# Adafruit_eInk_Feather_Friend.net
KiCad netlist of a schematic drawn in EAGLE
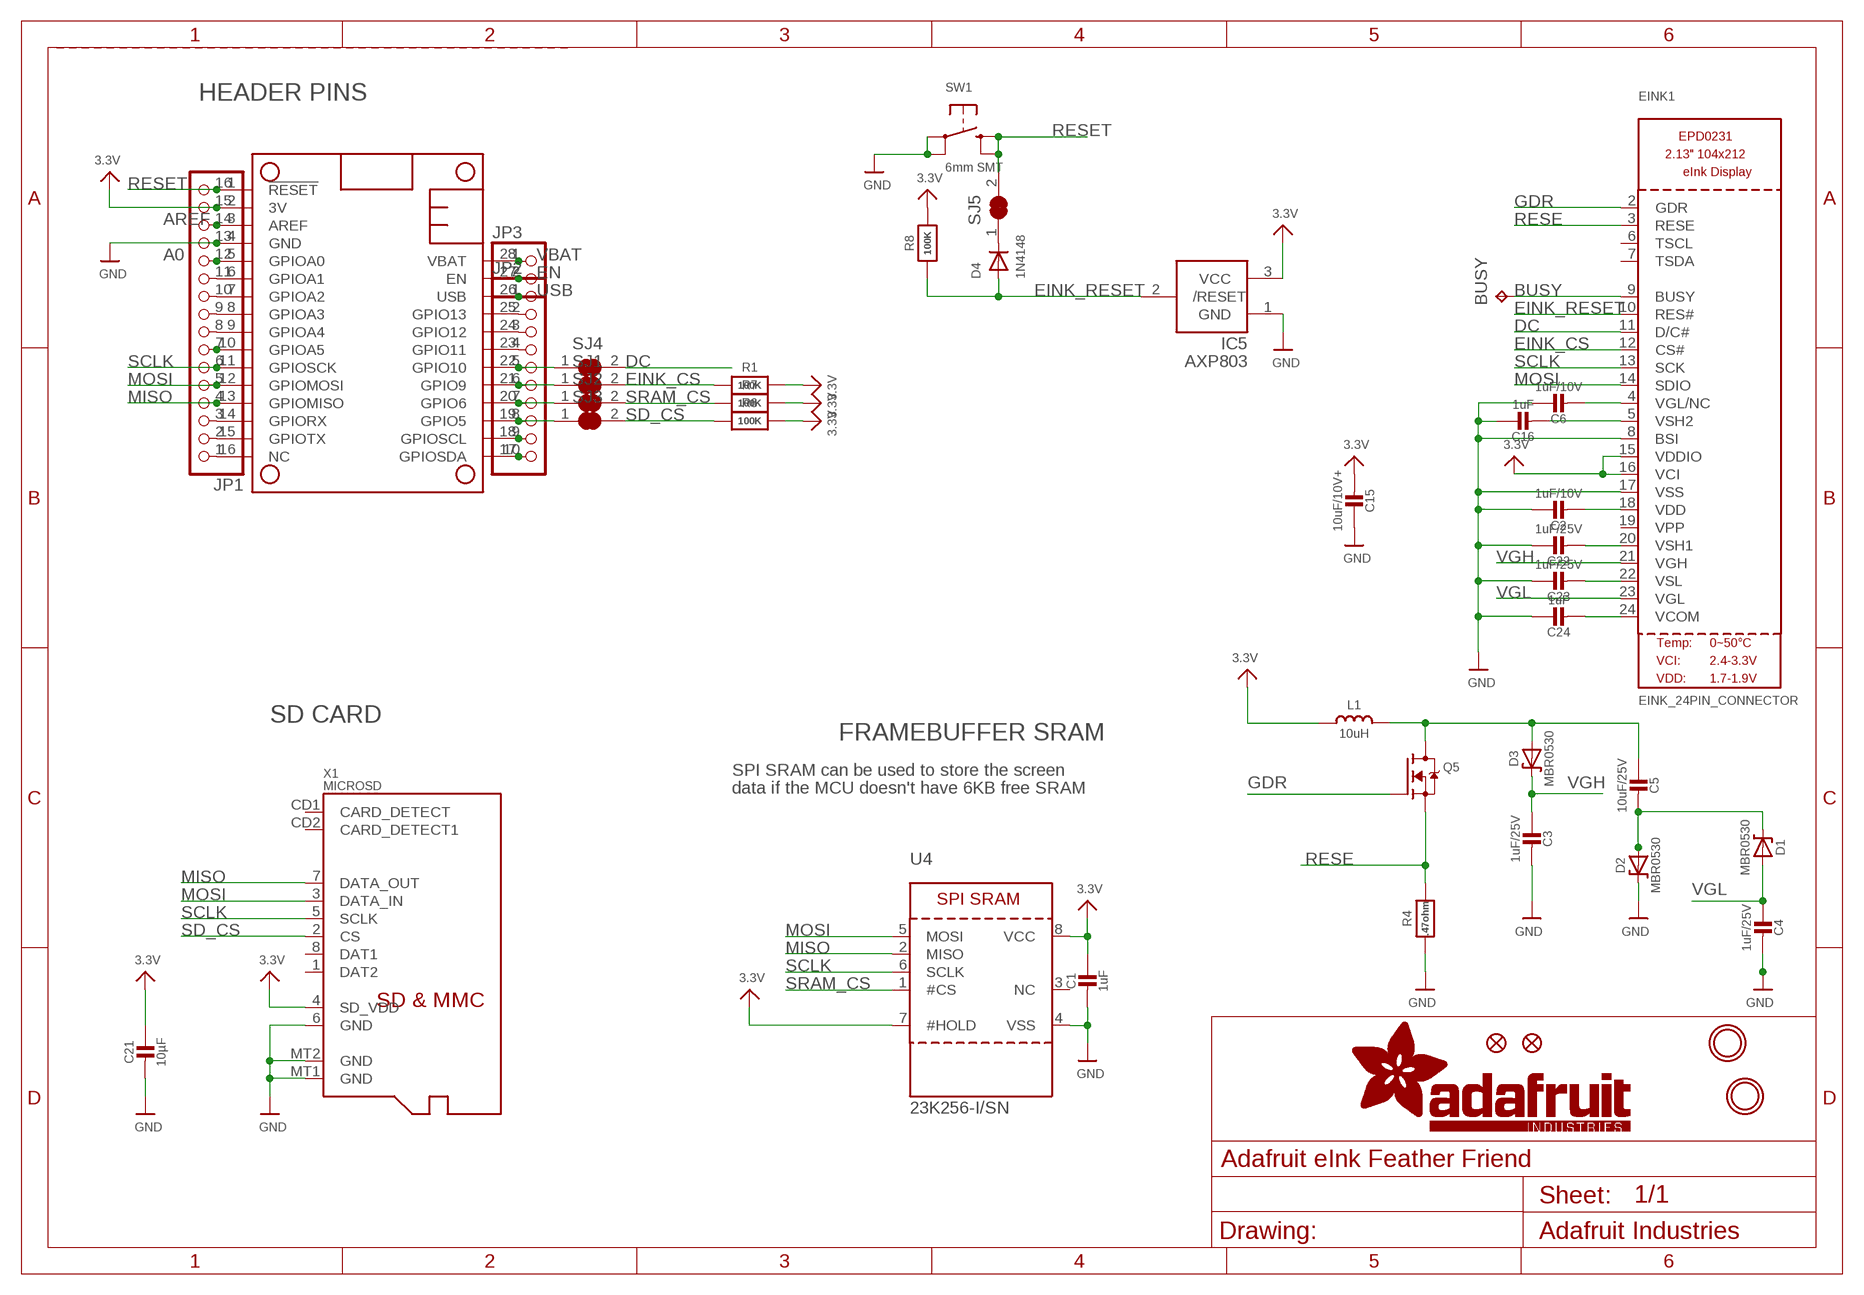
[diagram p0: schematic, sheet 1]

(export (version "E")
  (design (tool "Eeschema 10.0.6"))
  (components
    (comp (ref "BUSY")
      (value "TPTP15SQ")
      (footprint "eagle-import:TP15SQ")
      (libsource (lib "eagle-import") (part "TPTP15SQ"))
    )
    (comp (ref "C1")
      (value "1uF")
      (footprint "eagle-import:0805_10MGAP")
      (fields (field (name "REV") "A"))
      (libsource (lib "eagle-import") (part "CAP_CERAMIC0805_10MGAP"))
    )
    (comp (ref "C2")
      (value "1uF/10V")
      (footprint "eagle-import:0805-NO")
      (libsource (lib "eagle-import") (part "CAP_CERAMIC0805-NOOUTLINE"))
    )
    (comp (ref "C3")
      (value "1uF/25V")
      (footprint "eagle-import:0805-NO")
      (libsource (lib "eagle-import") (part "CAP_CERAMIC0805-NOOUTLINE"))
    )
    (comp (ref "C4")
      (value "1uF/25V")
      (footprint "eagle-import:0805-NO")
      (libsource (lib "eagle-import") (part "CAP_CERAMIC0805-NOOUTLINE"))
    )
    (comp (ref "C5")
      (value "10uF/25V")
      (footprint "eagle-import:0805-NO")
      (libsource (lib "eagle-import") (part "CAP_CERAMIC0805-NOOUTLINE"))
    )
    (comp (ref "C6")
      (value "1uF/10V")
      (footprint "eagle-import:0805-NO")
      (libsource (lib "eagle-import") (part "CAP_CERAMIC0805-NOOUTLINE"))
    )
    (comp (ref "C15")
      (value "10uF/10V+")
      (footprint "eagle-import:0805-NO")
      (libsource (lib "eagle-import") (part "CAP_CERAMIC0805-NOOUTLINE"))
    )
    (comp (ref "C16")
      (value "1uF")
      (footprint "eagle-import:0805-NO")
      (libsource (lib "eagle-import") (part "CAP_CERAMIC0805-NOOUTLINE"))
    )
    (comp (ref "C21")
      (value "10µF")
      (footprint "eagle-import:0805-NO")
      (libsource (lib "eagle-import") (part "CAP_CERAMIC0805-NOOUTLINE"))
    )
    (comp (ref "C22")
      (value "1uF/25V")
      (footprint "eagle-import:0805-NO")
      (libsource (lib "eagle-import") (part "CAP_CERAMIC0805-NOOUTLINE"))
    )
    (comp (ref "C23")
      (value "1uF/25V")
      (footprint "eagle-import:0805-NO")
      (libsource (lib "eagle-import") (part "CAP_CERAMIC0805-NOOUTLINE"))
    )
    (comp (ref "C24")
      (value "1uF")
      (footprint "eagle-import:0805-NO")
      (libsource (lib "eagle-import") (part "CAP_CERAMIC0805-NOOUTLINE"))
    )
    (comp (ref "D1")
      (value "MBR0530")
      (footprint "eagle-import:SOD-123")
      (libsource (lib "eagle-import") (part "DIODE-SCHOTTKYSOD-123"))
    )
    (comp (ref "D2")
      (value "MBR0530")
      (footprint "eagle-import:SOD-123")
      (libsource (lib "eagle-import") (part "DIODE-SCHOTTKYSOD-123"))
    )
    (comp (ref "D3")
      (value "MBR0530")
      (footprint "eagle-import:SOD-123")
      (libsource (lib "eagle-import") (part "DIODE-SCHOTTKYSOD-123"))
    )
    (comp (ref "D4")
      (value "1N4148")
      (footprint "eagle-import:SOD-323F")
      (libsource (lib "eagle-import") (part "DIODESOD-323F"))
    )
    (comp (ref "EINK1")
      (value "EINK_24PIN_CONNECTOR")
      (footprint "eagle-import:EINK_24PIN")
      (libsource (lib "eagle-import") (part "EINK_24PIN_CONNECTOR"))
    )
    (comp (ref "FID1")
      (value "FIDUCIAL_1MM")
      (footprint "eagle-import:FIDUCIAL_1MM")
      (libsource (lib "eagle-import") (part "FIDUCIAL_1MM"))
    )
    (comp (ref "FID3")
      (value "FIDUCIAL_1MM")
      (footprint "eagle-import:FIDUCIAL_1MM")
      (libsource (lib "eagle-import") (part "FIDUCIAL_1MM"))
    )
    (comp (ref "IC5")
      (value "AXP803")
      (footprint "eagle-import:SOT23")
      (libsource (lib "eagle-import") (part "AXP083-SAG"))
    )
    (comp (ref "JP1")
      (value "HEADER-1X16ROUND")
      (footprint "eagle-import:1X16_ROUND")
      (libsource (lib "eagle-import") (part "HEADER-1X16ROUND"))
    )
    (comp (ref "JP2")
      (value "HEADER-1X10ROUND")
      (footprint "eagle-import:1X10_ROUND")
      (libsource (lib "eagle-import") (part "HEADER-1X10ROUND"))
    )
    (comp (ref "JP3")
      (value "HEADER-1X2ROUND")
      (footprint "eagle-import:1X02_ROUND")
      (libsource (lib "eagle-import") (part "HEADER-1X2ROUND"))
    )
    (comp (ref "L1")
      (value "10uH")
      (footprint "eagle-import:INDUCTOR_4X4MM_NR401")
      (libsource (lib "eagle-import") (part "INDUCTORNR401"))
    )
    (comp (ref "MS1")
      (value "FEATHERWING_NOHOLES")
      (footprint "eagle-import:FEATHERWING_NOHOLES")
      (libsource (lib "eagle-import") (part "FEATHERWING_NOHOLES"))
    )
    (comp (ref "Q5")
      (value "IRLML0100")
      (footprint "eagle-import:SOT23-3")
      (libsource (lib "eagle-import") (part "IRLML2060TRPBF"))
    )
    (comp (ref "R1")
      (value "100K")
      (footprint "eagle-import:0603-NO")
      (libsource (lib "eagle-import") (part "RESISTOR_0603_NOOUT"))
    )
    (comp (ref "R4")
      (value ".47ohm")
      (footprint "eagle-import:0805_10MGAP")
      (libsource (lib "eagle-import") (part "RESISTOR0805_10MGAP"))
    )
    (comp (ref "R6")
      (value "100K")
      (footprint "eagle-import:0603-NO")
      (libsource (lib "eagle-import") (part "RESISTOR_0603_NOOUT"))
    )
    (comp (ref "R7")
      (value "100K")
      (footprint "eagle-import:0603-NO")
      (libsource (lib "eagle-import") (part "RESISTOR_0603_NOOUT"))
    )
    (comp (ref "R8")
      (value "100K")
      (footprint "eagle-import:0603-NO")
      (libsource (lib "eagle-import") (part "RESISTOR_0603_NOOUT"))
    )
    (comp (ref "SJ1")
      (value "SOLDERJUMPER_CLOSED")
      (footprint "eagle-import:SOLDERJUMPER_CLOSEDWIRE")
      (libsource (lib "eagle-import") (part "SOLDERJUMPER_CLOSED"))
    )
    (comp (ref "SJ2")
      (value "SOLDERJUMPER_CLOSED")
      (footprint "eagle-import:SOLDERJUMPER_CLOSEDWIRE")
      (libsource (lib "eagle-import") (part "SOLDERJUMPER_CLOSED"))
    )
    (comp (ref "SJ3")
      (value "SOLDERJUMPER_CLOSED")
      (footprint "eagle-import:SOLDERJUMPER_CLOSEDWIRE")
      (libsource (lib "eagle-import") (part "SOLDERJUMPER_CLOSED"))
    )
    (comp (ref "SJ4")
      (value "SOLDERJUMPER_CLOSED")
      (footprint "eagle-import:SOLDERJUMPER_CLOSEDWIRE")
      (libsource (lib "eagle-import") (part "SOLDERJUMPER_CLOSED"))
    )
    (comp (ref "SJ5")
      (value "SOLDERJUMPER_CLOSED")
      (footprint "eagle-import:SOLDERJUMPER_CLOSEDWIRE")
      (libsource (lib "eagle-import") (part "SOLDERJUMPER_CLOSED"))
    )
    (comp (ref "SW1")
      (value "6mm SMT")
      (footprint "eagle-import:BTN_KMR2_4.6X2.8")
      (libsource (lib "eagle-import") (part "SWITCH_TACT_SMT4.6X2.8"))
    )
    (comp (ref "U$3")
      (value "MOUNTINGHOLE2.5")
      (footprint "eagle-import:MOUNTINGHOLE_2.5_PLATED")
      (libsource (lib "eagle-import") (part "MOUNTINGHOLE2.5"))
    )
    (comp (ref "U$4")
      (value "MOUNTINGHOLE2.5")
      (footprint "eagle-import:MOUNTINGHOLE_2.5_PLATED")
      (libsource (lib "eagle-import") (part "MOUNTINGHOLE2.5"))
    )
    (comp (ref "U4")
      (value "23K256-I/SN")
      (footprint "eagle-import:SOIC8_150MIL")
      (libsource (lib "eagle-import") (part "SRAM_SPI_SOIC8"))
    )
    (comp (ref "X1")
      (value "MICROSD")
      (footprint "eagle-import:MICROSD")
      (libsource (lib "eagle-import") (part "MICROSD"))
    )
  )
  (nets
    (net (code "3") (name "/A0") (class "Default")
      (node (ref "JP1") (pin "12") (pinfunction "12_12") (pintype "passive"))
      (node (ref "MS1") (pin "5") (pinfunction "GPIOA0_5") (pintype "bidirectional"))
    )
    (net (code "4") (name "/AREF") (class "Default")
      (node (ref "JP1") (pin "14") (pinfunction "14_14") (pintype "passive"))
      (node (ref "MS1") (pin "3") (pinfunction "AREF_3") (pintype "passive"))
    )
    (net (code "5") (name "/BUSY") (class "Default")
      (node (ref "BUSY") (pin "TP") (pinfunction "TP_TP") (pintype "input"))
      (node (ref "EINK1") (pin "9") (pinfunction "BUSY_9") (pintype "output"))
    )
    (net (code "6") (name "/DC") (class "Default")
      (node (ref "EINK1") (pin "11") (pinfunction "D/C#_11") (pintype "input"))
      (node (ref "SJ4") (pin "2") (pinfunction "2_2") (pintype "passive"))
    )
    (net (code "8") (name "/EINK_CS") (class "Default")
      (node (ref "EINK1") (pin "12") (pinfunction "CS#_12") (pintype "input"))
      (node (ref "R1") (pin "1") (pinfunction "1_1") (pintype "passive"))
      (node (ref "SJ1") (pin "2") (pinfunction "2_2") (pintype "passive"))
    )
    (net (code "9") (name "/EINK_RESET") (class "Default")
      (node (ref "D4") (pin "A") (pinfunction "A_A") (pintype "passive"))
      (node (ref "EINK1") (pin "10") (pinfunction "RES#_10") (pintype "input"))
      (node (ref "IC5") (pin "2") (pinfunction "/RESET_2") (pintype "output"))
      (node (ref "R8") (pin "1") (pinfunction "1_1") (pintype "passive"))
    )
    (net (code "10") (name "/EN") (class "Default")
      (node (ref "JP3") (pin "2") (pinfunction "2_2") (pintype "passive"))
      (node (ref "MS1") (pin "27") (pinfunction "EN_27") (pintype "passive"))
    )
    (net (code "11") (name "/GDR") (class "Default")
      (node (ref "EINK1") (pin "2") (pinfunction "GDR_2") (pintype "output"))
      (node (ref "Q5") (pin "1") (pinfunction "G_1") (pintype "bidirectional"))
    )
    (net (code "12") (name "/MISO") (class "Default")
      (node (ref "JP1") (pin "4") (pinfunction "4_4") (pintype "passive"))
      (node (ref "MS1") (pin "13") (pinfunction "GPIOMISO_13") (pintype "bidirectional"))
      (node (ref "U4") (pin "2") (pinfunction "MISO_2") (pintype "output"))
      (node (ref "X1") (pin "7") (pinfunction "DATA_OUT_7") (pintype "output"))
    )
    (net (code "13") (name "/MOSI") (class "Default")
      (node (ref "EINK1") (pin "14") (pinfunction "SDIO_14") (pintype "bidirectional"))
      (node (ref "JP1") (pin "5") (pinfunction "5_5") (pintype "passive"))
      (node (ref "MS1") (pin "12") (pinfunction "GPIOMOSI_12") (pintype "bidirectional"))
      (node (ref "U4") (pin "5") (pinfunction "MOSI_5") (pintype "input"))
      (node (ref "X1") (pin "3") (pinfunction "DATA_IN_3") (pintype "input"))
    )
    (net (code "14") (name "/RESE") (class "Default")
      (node (ref "EINK1") (pin "3") (pinfunction "RESE_3") (pintype "input"))
      (node (ref "Q5") (pin "2") (pinfunction "S_2") (pintype "bidirectional"))
      (node (ref "R4") (pin "1") (pinfunction "1_1") (pintype "passive"))
    )
    (net (code "15") (name "/RESET") (class "Default")
      (node (ref "JP1") (pin "16") (pinfunction "16_16") (pintype "passive"))
      (node (ref "MS1") (pin "1") (pinfunction "~{RESET}_1") (pintype "input"))
      (node (ref "SJ5") (pin "2") (pinfunction "2_2") (pintype "passive"))
      (node (ref "SW1") (pin "B") (pinfunction "S_B") (pintype "passive"))
      (node (ref "SW1") (pin "B'") (pinfunction "S1_B'") (pintype "passive"))
    )
    (net (code "18") (name "/SCLK") (class "Default")
      (node (ref "EINK1") (pin "13") (pinfunction "SCK_13") (pintype "bidirectional"))
      (node (ref "JP1") (pin "6") (pinfunction "6_6") (pintype "passive"))
      (node (ref "MS1") (pin "11") (pinfunction "GPIOSCK_11") (pintype "bidirectional"))
      (node (ref "U4") (pin "6") (pinfunction "SCLK_6") (pintype "input"))
      (node (ref "X1") (pin "5") (pinfunction "SCLK_5") (pintype "input"))
    )
    (net (code "19") (name "/SD_CS") (class "Default")
      (node (ref "R6") (pin "1") (pinfunction "1_1") (pintype "passive"))
      (node (ref "SJ3") (pin "2") (pinfunction "2_2") (pintype "passive"))
      (node (ref "X1") (pin "2") (pinfunction "CS_2") (pintype "input"))
    )
    (net (code "20") (name "/SRAM_CS") (class "Default")
      (node (ref "R7") (pin "1") (pinfunction "1_1") (pintype "passive"))
      (node (ref "SJ2") (pin "2") (pinfunction "2_2") (pintype "passive"))
      (node (ref "U4") (pin "1") (pinfunction "#CS_1") (pintype "input"))
    )
    (net (code "21") (name "/USB") (class "Default")
      (node (ref "JP2") (pin "1") (pinfunction "1_1") (pintype "passive"))
      (node (ref "MS1") (pin "26") (pinfunction "USB_26") (pintype "power_in"))
    )
    (net (code "22") (name "/VBAT") (class "Default")
      (node (ref "JP3") (pin "1") (pinfunction "1_1") (pintype "passive"))
      (node (ref "MS1") (pin "28") (pinfunction "VBAT_28") (pintype "power_in"))
    )
    (net (code "23") (name "/VGH") (class "Default")
      (node (ref "C3") (pin "1") (pinfunction "1_1") (pintype "passive"))
      (node (ref "D3") (pin "C") (pinfunction "C_C") (pintype "passive"))
      (node (ref "EINK1") (pin "21") (pinfunction "VGH_21") (pintype "passive"))
    )
    (net (code "24") (name "/VGL") (class "Default")
      (node (ref "C4") (pin "1") (pinfunction "1_1") (pintype "passive"))
      (node (ref "D1") (pin "A") (pinfunction "A_A") (pintype "passive"))
      (node (ref "EINK1") (pin "23") (pinfunction "VGL_23") (pintype "passive"))
    )
    (net (code "25") (name "3.3V") (class "Default")
      (node (ref "C1") (pin "1") (pinfunction "1_1") (pintype "passive"))
      (node (ref "C15") (pin "2") (pinfunction "2_2") (pintype "passive"))
      (node (ref "C21") (pin "1") (pinfunction "1_1") (pintype "passive"))
      (node (ref "EINK1") (pin "15") (pinfunction "VDDIO_15") (pintype "power_in"))
      (node (ref "EINK1") (pin "16") (pinfunction "VCI_16") (pintype "power_in"))
      (node (ref "IC5") (pin "3") (pinfunction "VCC_3") (pintype "power_in"))
      (node (ref "JP1") (pin "15") (pinfunction "15_15") (pintype "passive"))
      (node (ref "L1") (pin "P$2") (pinfunction "2_P$2") (pintype "passive"))
      (node (ref "MS1") (pin "2") (pinfunction "3V_2") (pintype "power_in"))
      (node (ref "R1") (pin "2") (pinfunction "2_2") (pintype "passive"))
      (node (ref "R6") (pin "2") (pinfunction "2_2") (pintype "passive"))
      (node (ref "R7") (pin "2") (pinfunction "2_2") (pintype "passive"))
      (node (ref "R8") (pin "2") (pinfunction "2_2") (pintype "passive"))
      (node (ref "U4") (pin "7") (pinfunction "#HOLD_7") (pintype "input"))
      (node (ref "U4") (pin "8") (pinfunction "VCC_8") (pintype "power_in"))
      (node (ref "X1") (pin "4") (pinfunction "SD_VDD_4") (pintype "power_in"))
    )
    (net (code "26") (name "GND") (class "Default")
      (node (ref "C1") (pin "2") (pinfunction "2_2") (pintype "passive"))
      (node (ref "C15") (pin "1") (pinfunction "1_1") (pintype "passive"))
      (node (ref "C16") (pin "1") (pinfunction "1_1") (pintype "passive"))
      (node (ref "C2") (pin "1") (pinfunction "1_1") (pintype "passive"))
      (node (ref "C21") (pin "2") (pinfunction "2_2") (pintype "passive"))
      (node (ref "C22") (pin "1") (pinfunction "1_1") (pintype "passive"))
      (node (ref "C23") (pin "1") (pinfunction "1_1") (pintype "passive"))
      (node (ref "C24") (pin "1") (pinfunction "1_1") (pintype "passive"))
      (node (ref "C3") (pin "2") (pinfunction "2_2") (pintype "passive"))
      (node (ref "C4") (pin "2") (pinfunction "2_2") (pintype "passive"))
      (node (ref "C6") (pin "1") (pinfunction "1_1") (pintype "passive"))
      (node (ref "D2") (pin "C") (pinfunction "C_C") (pintype "passive"))
      (node (ref "EINK1") (pin "17") (pinfunction "VSS_17") (pintype "power_in"))
      (node (ref "EINK1") (pin "8") (pinfunction "BSI_8") (pintype "input"))
      (node (ref "IC5") (pin "1") (pinfunction "GND_1") (pintype "power_in"))
      (node (ref "JP1") (pin "13") (pinfunction "13_13") (pintype "passive"))
      (node (ref "MS1") (pin "4") (pinfunction "GND_4") (pintype "power_in"))
      (node (ref "R4") (pin "2") (pinfunction "2_2") (pintype "passive"))
      (node (ref "SW1") (pin "A") (pinfunction "P_A") (pintype "passive"))
      (node (ref "SW1") (pin "A'") (pinfunction "P1_A'") (pintype "passive"))
      (node (ref "U4") (pin "4") (pinfunction "VSS_4") (pintype "power_in"))
      (node (ref "X1") (pin "6") (pinfunction "GND_6") (pintype "power_in"))
      (node (ref "X1") (pin "MT1") (pinfunction "GND_MT1") (pintype "power_in"))
      (node (ref "X1") (pin "MT2") (pinfunction "GND_MT2") (pintype "power_in"))
    )
    (net (code "27") (name "Net-(C5-Pad2)") (class "Default")
      (node (ref "C5") (pin "2") (pinfunction "2_2") (pintype "passive"))
      (node (ref "D1") (pin "C") (pinfunction "C_C") (pintype "passive"))
      (node (ref "D2") (pin "A") (pinfunction "A_A") (pintype "passive"))
    )
    (net (code "28") (name "Net-(D4-PadC)") (class "Default")
      (node (ref "D4") (pin "C") (pinfunction "C_C") (pintype "passive"))
      (node (ref "SJ5") (pin "1") (pinfunction "1_1") (pintype "passive"))
    )
    (net (code "29") (name "Net-(EINK1-VCOM)") (class "Default")
      (node (ref "C24") (pin "2") (pinfunction "2_2") (pintype "passive"))
      (node (ref "EINK1") (pin "24") (pinfunction "VCOM_24") (pintype "passive"))
    )
    (net (code "30") (name "Net-(EINK1-VDD)") (class "Default")
      (node (ref "C2") (pin "2") (pinfunction "2_2") (pintype "passive"))
      (node (ref "EINK1") (pin "18") (pinfunction "VDD_18") (pintype "passive"))
    )
    (net (code "31") (name "Net-(EINK1-VGL{slash}NC)") (class "Default")
      (node (ref "C6") (pin "2") (pinfunction "2_2") (pintype "passive"))
      (node (ref "EINK1") (pin "4") (pinfunction "VGL/NC_4") (pintype "bidirectional"))
    )
    (net (code "32") (name "Net-(EINK1-VSH1)") (class "Default")
      (node (ref "C22") (pin "2") (pinfunction "2_2") (pintype "passive"))
      (node (ref "EINK1") (pin "20") (pinfunction "VSH1_20") (pintype "passive"))
    )
    (net (code "33") (name "Net-(EINK1-VSH2)") (class "Default")
      (node (ref "C16") (pin "2") (pinfunction "2_2") (pintype "passive"))
      (node (ref "EINK1") (pin "5") (pinfunction "VSH2_5") (pintype "passive"))
    )
    (net (code "34") (name "Net-(EINK1-VSL)") (class "Default")
      (node (ref "C23") (pin "2") (pinfunction "2_2") (pintype "passive"))
      (node (ref "EINK1") (pin "22") (pinfunction "VSL_22") (pintype "passive"))
    )
    (net (code "35") (name "Net-(L1-1)") (class "Default")
      (node (ref "C5") (pin "1") (pinfunction "1_1") (pintype "passive"))
      (node (ref "D3") (pin "A") (pinfunction "A_A") (pintype "passive"))
      (node (ref "L1") (pin "P$1") (pinfunction "1_P$1") (pintype "passive"))
      (node (ref "Q5") (pin "3") (pinfunction "D_3") (pintype "bidirectional"))
    )
    (net (code "36") (name "Net-(MS1-GPIO5)") (class "Default")
      (node (ref "JP2") (pin "8") (pinfunction "8_8") (pintype "passive"))
      (node (ref "MS1") (pin "19") (pinfunction "GPIO5_19") (pintype "bidirectional"))
      (node (ref "SJ3") (pin "1") (pinfunction "1_1") (pintype "passive"))
    )
    (net (code "37") (name "Net-(MS1-GPIO6)") (class "Default")
      (node (ref "JP2") (pin "7") (pinfunction "7_7") (pintype "passive"))
      (node (ref "MS1") (pin "20") (pinfunction "GPIO6_20") (pintype "bidirectional"))
      (node (ref "SJ2") (pin "1") (pinfunction "1_1") (pintype "passive"))
    )
    (net (code "38") (name "Net-(MS1-GPIO9)") (class "Default")
      (node (ref "JP2") (pin "6") (pinfunction "6_6") (pintype "passive"))
      (node (ref "MS1") (pin "21") (pinfunction "GPIO9_21") (pintype "bidirectional"))
      (node (ref "SJ1") (pin "1") (pinfunction "1_1") (pintype "passive"))
    )
    (net (code "39") (name "Net-(MS1-GPIO10)") (class "Default")
      (node (ref "JP2") (pin "5") (pinfunction "5_5") (pintype "passive"))
      (node (ref "MS1") (pin "22") (pinfunction "GPIO10_22") (pintype "bidirectional"))
      (node (ref "SJ4") (pin "1") (pinfunction "1_1") (pintype "passive"))
    )
    (net (code "40") (name "Net-(MS1-GPIO11)") (class "Default")
      (node (ref "JP2") (pin "4") (pinfunction "4_4") (pintype "passive"))
      (node (ref "MS1") (pin "23") (pinfunction "GPIO11_23") (pintype "bidirectional"))
    )
    (net (code "41") (name "Net-(MS1-GPIO12)") (class "Default")
      (node (ref "JP2") (pin "3") (pinfunction "3_3") (pintype "passive"))
      (node (ref "MS1") (pin "24") (pinfunction "GPIO12_24") (pintype "bidirectional"))
    )
    (net (code "42") (name "Net-(MS1-GPIO13)") (class "Default")
      (node (ref "JP2") (pin "2") (pinfunction "2_2") (pintype "passive"))
      (node (ref "MS1") (pin "25") (pinfunction "GPIO13_25") (pintype "bidirectional"))
    )
    (net (code "43") (name "Net-(MS1-GPIOA1)") (class "Default")
      (node (ref "JP1") (pin "11") (pinfunction "11_11") (pintype "passive"))
      (node (ref "MS1") (pin "6") (pinfunction "GPIOA1_6") (pintype "bidirectional"))
    )
    (net (code "44") (name "Net-(MS1-GPIOA2)") (class "Default")
      (node (ref "JP1") (pin "10") (pinfunction "10_10") (pintype "passive"))
      (node (ref "MS1") (pin "7") (pinfunction "GPIOA2_7") (pintype "bidirectional"))
    )
    (net (code "45") (name "Net-(MS1-GPIOA3)") (class "Default")
      (node (ref "JP1") (pin "9") (pinfunction "9_9") (pintype "passive"))
      (node (ref "MS1") (pin "8") (pinfunction "GPIOA3_8") (pintype "bidirectional"))
    )
    (net (code "46") (name "Net-(MS1-GPIOA4)") (class "Default")
      (node (ref "JP1") (pin "8") (pinfunction "8_8") (pintype "passive"))
      (node (ref "MS1") (pin "9") (pinfunction "GPIOA4_9") (pintype "bidirectional"))
    )
    (net (code "47") (name "Net-(MS1-GPIOA5)") (class "Default")
      (node (ref "JP1") (pin "7") (pinfunction "7_7") (pintype "passive"))
      (node (ref "MS1") (pin "10") (pinfunction "GPIOA5_10") (pintype "bidirectional"))
    )
    (net (code "48") (name "Net-(MS1-GPIORX)") (class "Default")
      (node (ref "JP1") (pin "3") (pinfunction "3_3") (pintype "passive"))
      (node (ref "MS1") (pin "14") (pinfunction "GPIORX_14") (pintype "bidirectional"))
    )
    (net (code "49") (name "Net-(MS1-GPIOSCL)") (class "Default")
      (node (ref "JP2") (pin "9") (pinfunction "9_9") (pintype "passive"))
      (node (ref "MS1") (pin "18") (pinfunction "GPIOSCL_18") (pintype "bidirectional"))
    )
    (net (code "50") (name "Net-(MS1-GPIOSDA)") (class "Default")
      (node (ref "JP2") (pin "10") (pinfunction "10_10") (pintype "passive"))
      (node (ref "MS1") (pin "17") (pinfunction "GPIOSDA_17") (pintype "bidirectional"))
    )
    (net (code "51") (name "Net-(MS1-GPIOTX)") (class "Default")
      (node (ref "JP1") (pin "2") (pinfunction "2_2") (pintype "passive"))
      (node (ref "MS1") (pin "15") (pinfunction "GPIOTX_15") (pintype "bidirectional"))
    )
    (net (code "52") (name "Net-(MS1-NC)") (class "Default")
      (node (ref "JP1") (pin "1") (pinfunction "1_1") (pintype "passive"))
      (node (ref "MS1") (pin "16") (pinfunction "NC_16") (pintype "passive"))
    )
    (net (code "53") (name "unconnected-(EINK1-TSCL-Pad6)") (class "Default")
      (node (ref "EINK1") (pin "6") (pinfunction "TSCL_6") (pintype "output"))
    )
    (net (code "54") (name "unconnected-(EINK1-TSDA-Pad7)") (class "Default")
      (node (ref "EINK1") (pin "7") (pinfunction "TSDA_7") (pintype "bidirectional"))
    )
    (net (code "55") (name "unconnected-(EINK1-VPP-Pad19)") (class "Default")
      (node (ref "EINK1") (pin "19") (pinfunction "VPP_19") (pintype "passive"))
    )
    (net (code "56") (name "unconnected-(U4-NC-Pad3)") (class "Default")
      (node (ref "U4") (pin "3") (pinfunction "NC_3") (pintype "no_connect"))
    )
    (net (code "57") (name "unconnected-(X1-CARD_DETECT-PadCD1)") (class "Default")
      (node (ref "X1") (pin "CD1") (pinfunction "CARD_DETECT_CD1") (pintype "passive"))
    )
    (net (code "58") (name "unconnected-(X1-CARD_DETECT1-PadCD2)") (class "Default")
      (node (ref "X1") (pin "CD2") (pinfunction "CARD_DETECT1_CD2") (pintype "passive"))
    )
    (net (code "59") (name "unconnected-(X1-DAT1-Pad8)") (class "Default")
      (node (ref "X1") (pin "8") (pinfunction "DAT1_8") (pintype "bidirectional"))
    )
    (net (code "60") (name "unconnected-(X1-DAT2-Pad1)") (class "Default")
      (node (ref "X1") (pin "1") (pinfunction "DAT2_1") (pintype "bidirectional"))
    )
  )
)
